# usb_connectors.net
KiCad netlist of a schematic drawn in Altium Designer
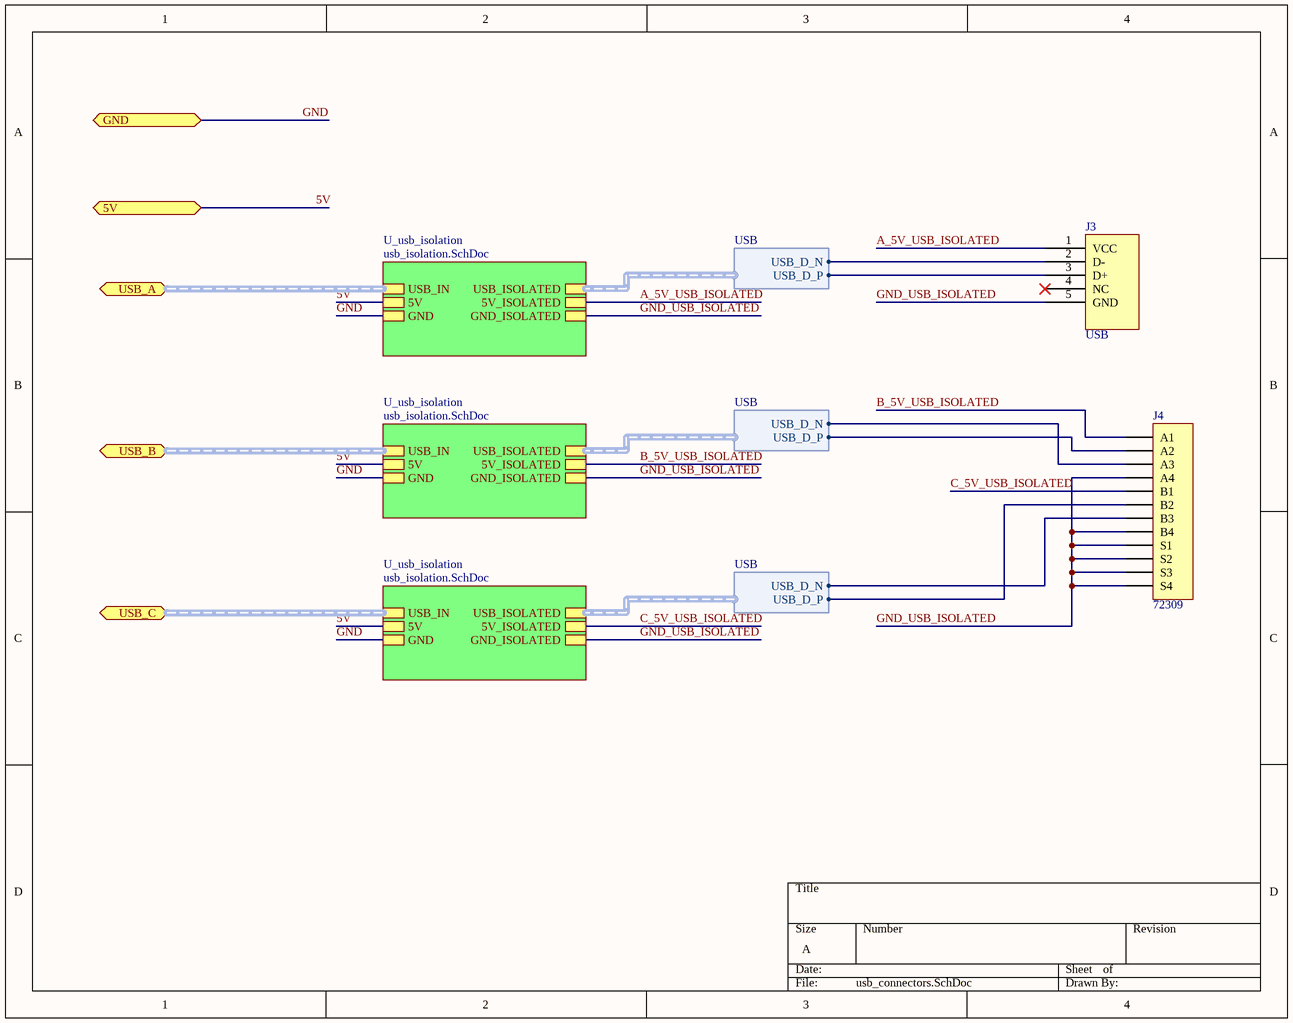
[diagram p0: usb_connectors.SchDoc]

(export (version "E")
  (design (tool "Eeschema 10.0.6"))
  (components
    (comp (ref "J3")
      (value "USB")
      (footprint "DX2R005HN2E700")
      (description "USB mini-B receptacle")
      (fields (field (name "MANUFACTURER") "JAE Electronics"))
      (libsource (lib "jae") (part "DX2R005HN2E700"))
    )
    (comp (ref "J4")
      (value "72309")
      (footprint "72309")
      (description "USB Double Deck Receptacle")
      (fields (field (name "MANUFACTURER") "FCI"))
      (libsource (lib "openrd") (part "72309"))
    )
  )
  (nets
    (net (code "6") (name "/A_5V_USB_ISOLATED") (class "Default")
      (node (ref "J3") (pin "1") (pinfunction "VCC_1") (pintype "passive"))
    )
    (net (code "7") (name "/B_5V_USB_ISOLATED") (class "Default")
      (node (ref "J4") (pin "A1") (pinfunction "A1_A1") (pintype "passive"))
    )
    (net (code "8") (name "/C_5V_USB_ISOLATED") (class "Default")
      (node (ref "J4") (pin "B1") (pinfunction "B1_B1") (pintype "passive"))
    )
    (net (code "10") (name "/GND_USB_ISOLATED") (class "Default")
      (node (ref "J3") (pin "5") (pinfunction "GND_5") (pintype "passive"))
      (node (ref "J4") (pin "A4") (pinfunction "A4_A4") (pintype "passive"))
      (node (ref "J4") (pin "B4") (pinfunction "B4_B4") (pintype "passive"))
      (node (ref "J4") (pin "S1") (pinfunction "S1_S1") (pintype "passive"))
      (node (ref "J4") (pin "S2") (pinfunction "S2_S2") (pintype "passive"))
      (node (ref "J4") (pin "S3") (pinfunction "S3_S3") (pintype "passive"))
      (node (ref "J4") (pin "S4") (pinfunction "S4_S4") (pintype "passive"))
    )
    (net (code "15") (name "unconnected-(J3-D+-Pad3)") (class "Default")
      (node (ref "J3") (pin "3") (pinfunction "D+_3") (pintype "passive"))
    )
    (net (code "16") (name "unconnected-(J3-D--Pad2)") (class "Default")
      (node (ref "J3") (pin "2") (pinfunction "D-_2") (pintype "passive"))
    )
    (net (code "17") (name "unconnected-(J3-NC-Pad4)") (class "Default")
      (node (ref "J3") (pin "4") (pinfunction "NC_4") (pintype "passive+no_connect"))
    )
    (net (code "18") (name "unconnected-(J4-PadA2)") (class "Default")
      (node (ref "J4") (pin "A2") (pinfunction "A2_A2") (pintype "passive"))
    )
    (net (code "19") (name "unconnected-(J4-PadA3)") (class "Default")
      (node (ref "J4") (pin "A3") (pinfunction "A3_A3") (pintype "passive"))
    )
    (net (code "20") (name "unconnected-(J4-PadB2)") (class "Default")
      (node (ref "J4") (pin "B2") (pinfunction "B2_B2") (pintype "passive"))
    )
    (net (code "21") (name "unconnected-(J4-PadB3)") (class "Default")
      (node (ref "J4") (pin "B3") (pinfunction "B3_B3") (pintype "passive"))
    )
  )
)
